# PCI-connector.net
KiCad netlist of a schematic drawn in Altium Designer
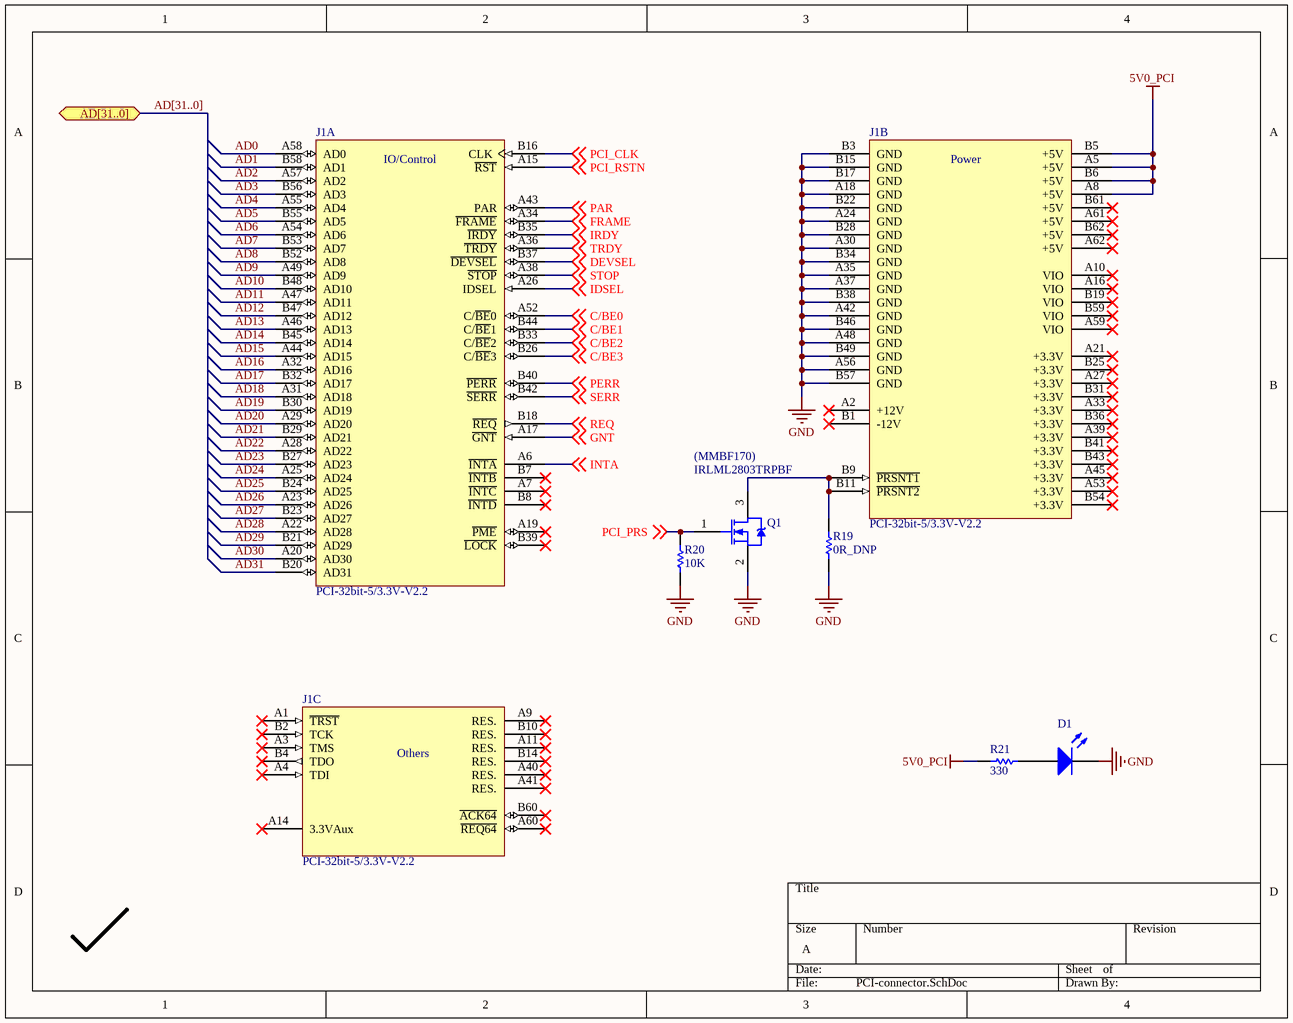
[diagram p0: PCI-connector.SchDoc]

(export (version "E")
  (design (tool "Eeschema 10.0.6"))
  (components
    (comp (ref "D1")
      (value "LED0")
      (footprint "C0805")
      (description "Typical INFRARED GaAs LED")
      (fields (field (name "PUBLISHER") "Altium Limited"))
      (libsource (lib "Miscellaneous Devices") (part "LED0"))
    )
    (comp (ref "J1")
      (value "PCI-32bit-5/3.3V-V2.2")
      (footprint "PCI-32bit-5/3.3V-V2.2")
      (libsource (lib "Conn_Schlib") (part "PCI-32bit-5/3.3V-V2.2"))
    )
    (comp (ref "Q1")
      (value "IRLML2803TRPBF")
      (footprint "SOT23")
      (description "N-Channel Power MOSFET")
      (fields (field (name "PUBLISHER") "Altium Limited"))
      (libsource (lib "Miscellaneous Devices") (part "NMOS-2"))
    )
    (comp (ref "R19")
      (value "0R_DNP")
      (footprint "0603PKG")
      (description "Semiconductor Resistor")
      (fields (field (name "Comment") "Res Semi") (field (name "PUBLISHER") "Altium Limited"))
      (libsource (lib "Miscellaneous Devices") (part "Res Semi"))
    )
    (comp (ref "R20")
      (value "10K")
      (footprint "0603PKG")
      (description "Semiconductor Resistor")
      (fields (field (name "Comment") "Res Semi") (field (name "PUBLISHER") "Altium Limited"))
      (libsource (lib "Miscellaneous Devices") (part "Res Semi"))
    )
    (comp (ref "R21")
      (value "330")
      (footprint "0603PKG")
      (description "Semiconductor Resistor")
      (fields (field (name "Comment") "Res Semi") (field (name "PUBLISHER") "Altium Limited"))
      (libsource (lib "Miscellaneous Devices") (part "Res Semi"))
    )
  )
  (nets
    (net (code "1") (name "/AD0") (class "Default")
      (node (ref "J1") (pin "A58") (pinfunction "AD0_A58") (pintype "bidirectional"))
    )
    (net (code "2") (name "/AD1") (class "Default")
      (node (ref "J1") (pin "B58") (pinfunction "AD1_B58") (pintype "bidirectional"))
    )
    (net (code "3") (name "/AD2") (class "Default")
      (node (ref "J1") (pin "A57") (pinfunction "AD2_A57") (pintype "bidirectional"))
    )
    (net (code "4") (name "/AD3") (class "Default")
      (node (ref "J1") (pin "B56") (pinfunction "AD3_B56") (pintype "bidirectional"))
    )
    (net (code "5") (name "/AD4") (class "Default")
      (node (ref "J1") (pin "A55") (pinfunction "AD4_A55") (pintype "bidirectional"))
    )
    (net (code "6") (name "/AD5") (class "Default")
      (node (ref "J1") (pin "B55") (pinfunction "AD5_B55") (pintype "bidirectional"))
    )
    (net (code "7") (name "/AD6") (class "Default")
      (node (ref "J1") (pin "A54") (pinfunction "AD6_A54") (pintype "bidirectional"))
    )
    (net (code "8") (name "/AD7") (class "Default")
      (node (ref "J1") (pin "B53") (pinfunction "AD7_B53") (pintype "bidirectional"))
    )
    (net (code "9") (name "/AD8") (class "Default")
      (node (ref "J1") (pin "B52") (pinfunction "AD8_B52") (pintype "bidirectional"))
    )
    (net (code "10") (name "/AD9") (class "Default")
      (node (ref "J1") (pin "A49") (pinfunction "AD9_A49") (pintype "bidirectional"))
    )
    (net (code "11") (name "/AD10") (class "Default")
      (node (ref "J1") (pin "B48") (pinfunction "AD10_B48") (pintype "bidirectional"))
    )
    (net (code "12") (name "/AD11") (class "Default")
      (node (ref "J1") (pin "A47") (pinfunction "AD11_A47") (pintype "bidirectional"))
    )
    (net (code "13") (name "/AD12") (class "Default")
      (node (ref "J1") (pin "B47") (pinfunction "AD12_B47") (pintype "bidirectional"))
    )
    (net (code "14") (name "/AD13") (class "Default")
      (node (ref "J1") (pin "A46") (pinfunction "AD13_A46") (pintype "bidirectional"))
    )
    (net (code "15") (name "/AD14") (class "Default")
      (node (ref "J1") (pin "B45") (pinfunction "AD14_B45") (pintype "bidirectional"))
    )
    (net (code "16") (name "/AD15") (class "Default")
      (node (ref "J1") (pin "A44") (pinfunction "AD15_A44") (pintype "bidirectional"))
    )
    (net (code "17") (name "/AD16") (class "Default")
      (node (ref "J1") (pin "A32") (pinfunction "AD16_A32") (pintype "bidirectional"))
    )
    (net (code "18") (name "/AD17") (class "Default")
      (node (ref "J1") (pin "B32") (pinfunction "AD17_B32") (pintype "bidirectional"))
    )
    (net (code "19") (name "/AD18") (class "Default")
      (node (ref "J1") (pin "A31") (pinfunction "AD18_A31") (pintype "bidirectional"))
    )
    (net (code "20") (name "/AD19") (class "Default")
      (node (ref "J1") (pin "B30") (pinfunction "AD19_B30") (pintype "bidirectional"))
    )
    (net (code "21") (name "/AD20") (class "Default")
      (node (ref "J1") (pin "A29") (pinfunction "AD20_A29") (pintype "bidirectional"))
    )
    (net (code "22") (name "/AD21") (class "Default")
      (node (ref "J1") (pin "B29") (pinfunction "AD21_B29") (pintype "bidirectional"))
    )
    (net (code "23") (name "/AD22") (class "Default")
      (node (ref "J1") (pin "A28") (pinfunction "AD22_A28") (pintype "bidirectional"))
    )
    (net (code "24") (name "/AD23") (class "Default")
      (node (ref "J1") (pin "B27") (pinfunction "AD23_B27") (pintype "bidirectional"))
    )
    (net (code "25") (name "/AD24") (class "Default")
      (node (ref "J1") (pin "A25") (pinfunction "AD24_A25") (pintype "bidirectional"))
    )
    (net (code "26") (name "/AD25") (class "Default")
      (node (ref "J1") (pin "B24") (pinfunction "AD25_B24") (pintype "bidirectional"))
    )
    (net (code "27") (name "/AD26") (class "Default")
      (node (ref "J1") (pin "A23") (pinfunction "AD26_A23") (pintype "bidirectional"))
    )
    (net (code "28") (name "/AD27") (class "Default")
      (node (ref "J1") (pin "B23") (pinfunction "AD27_B23") (pintype "bidirectional"))
    )
    (net (code "29") (name "/AD28") (class "Default")
      (node (ref "J1") (pin "A22") (pinfunction "AD28_A22") (pintype "bidirectional"))
    )
    (net (code "30") (name "/AD29") (class "Default")
      (node (ref "J1") (pin "B21") (pinfunction "AD29_B21") (pintype "bidirectional"))
    )
    (net (code "31") (name "/AD30") (class "Default")
      (node (ref "J1") (pin "A20") (pinfunction "AD30_A20") (pintype "bidirectional"))
    )
    (net (code "32") (name "/AD31") (class "Default")
      (node (ref "J1") (pin "B20") (pinfunction "AD31_B20") (pintype "bidirectional"))
    )
    (net (code "34") (name "5V0_PCI") (class "Default")
      (node (ref "J1") (pin "A5") (pinfunction "+5V_A5") (pintype "power_in"))
      (node (ref "J1") (pin "A8") (pinfunction "+5V_A8") (pintype "power_in"))
      (node (ref "J1") (pin "B5") (pinfunction "+5V_B5") (pintype "power_in"))
      (node (ref "J1") (pin "B6") (pinfunction "+5V_B6") (pintype "power_in"))
      (node (ref "R21") (pin "2") (pinfunction "2_2") (pintype "passive"))
    )
    (net (code "35") (name "C{slash}BE0") (class "Default")
      (node (ref "J1") (pin "A52") (pinfunction "C/~{BE}0_A52") (pintype "bidirectional"))
    )
    (net (code "36") (name "C{slash}BE1") (class "Default")
      (node (ref "J1") (pin "B44") (pinfunction "C/~{BE}1_B44") (pintype "bidirectional"))
    )
    (net (code "37") (name "C{slash}BE2") (class "Default")
      (node (ref "J1") (pin "B33") (pinfunction "C/~{BE}2_B33") (pintype "bidirectional"))
    )
    (net (code "38") (name "C{slash}BE3") (class "Default")
      (node (ref "J1") (pin "B26") (pinfunction "C/~{BE}3_B26") (pintype "bidirectional"))
    )
    (net (code "39") (name "DEVSEL") (class "Default")
      (node (ref "J1") (pin "B37") (pinfunction "~{DEVSEL}_B37") (pintype "bidirectional"))
    )
    (net (code "40") (name "FRAME") (class "Default")
      (node (ref "J1") (pin "A34") (pinfunction "~{FRAME}_A34") (pintype "bidirectional"))
    )
    (net (code "41") (name "GND") (class "Default")
      (node (ref "D1") (pin "2") (pinfunction "K_2") (pintype "passive"))
      (node (ref "J1") (pin "A18") (pinfunction "GND_A18") (pintype "power_in"))
      (node (ref "J1") (pin "A24") (pinfunction "GND_A24") (pintype "power_in"))
      (node (ref "J1") (pin "A30") (pinfunction "GND_A30") (pintype "power_in"))
      (node (ref "J1") (pin "A35") (pinfunction "GND_A35") (pintype "power_in"))
      (node (ref "J1") (pin "A37") (pinfunction "GND_A37") (pintype "power_in"))
      (node (ref "J1") (pin "A42") (pinfunction "GND_A42") (pintype "power_in"))
      (node (ref "J1") (pin "A48") (pinfunction "GND_A48") (pintype "power_in"))
      (node (ref "J1") (pin "A56") (pinfunction "GND_A56") (pintype "power_in"))
      (node (ref "J1") (pin "B15") (pinfunction "GND_B15") (pintype "power_in"))
      (node (ref "J1") (pin "B17") (pinfunction "GND_B17") (pintype "power_in"))
      (node (ref "J1") (pin "B22") (pinfunction "GND_B22") (pintype "power_in"))
      (node (ref "J1") (pin "B28") (pinfunction "GND_B28") (pintype "power_in"))
      (node (ref "J1") (pin "B3") (pinfunction "GND_B3") (pintype "power_in"))
      (node (ref "J1") (pin "B34") (pinfunction "GND_B34") (pintype "power_in"))
      (node (ref "J1") (pin "B38") (pinfunction "GND_B38") (pintype "power_in"))
      (node (ref "J1") (pin "B46") (pinfunction "GND_B46") (pintype "power_in"))
      (node (ref "J1") (pin "B49") (pinfunction "GND_B49") (pintype "power_in"))
      (node (ref "J1") (pin "B57") (pinfunction "GND_B57") (pintype "power_in"))
      (node (ref "Q1") (pin "2") (pinfunction "S_2") (pintype "passive"))
      (node (ref "R19") (pin "2") (pinfunction "2_2") (pintype "passive"))
      (node (ref "R20") (pin "2") (pinfunction "2_2") (pintype "passive"))
    )
    (net (code "42") (name "GNT") (class "Default")
      (node (ref "J1") (pin "A17") (pinfunction "~{GNT}_A17") (pintype "input"))
    )
    (net (code "43") (name "IDSEL") (class "Default")
      (node (ref "J1") (pin "A26") (pinfunction "IDSEL_A26") (pintype "input"))
    )
    (net (code "44") (name "INTA") (class "Default")
      (node (ref "J1") (pin "A6") (pinfunction "~{INTA}_A6") (pintype "open_collector"))
    )
    (net (code "45") (name "IRDY") (class "Default")
      (node (ref "J1") (pin "B35") (pinfunction "~{IRDY}_B35") (pintype "bidirectional"))
    )
    (net (code "46") (name "Net-(D1-A)") (class "Default")
      (node (ref "D1") (pin "1") (pinfunction "A_1") (pintype "passive"))
      (node (ref "R21") (pin "1") (pinfunction "1_1") (pintype "passive"))
    )
    (net (code "47") (name "Net-(J1B-~{PRSNT1})") (class "Default")
      (node (ref "J1") (pin "B11") (pinfunction "~{PRSNT2}_B11") (pintype "input"))
      (node (ref "J1") (pin "B9") (pinfunction "~{PRSNT1}_B9") (pintype "input"))
      (node (ref "Q1") (pin "3") (pinfunction "D_3") (pintype "passive"))
      (node (ref "R19") (pin "1") (pinfunction "1_1") (pintype "passive"))
    )
    (net (code "48") (name "PAR") (class "Default")
      (node (ref "J1") (pin "A43") (pinfunction "PAR_A43") (pintype "bidirectional"))
    )
    (net (code "49") (name "PCI_CLK") (class "Default")
      (node (ref "J1") (pin "B16") (pinfunction "CLK_B16") (pintype "input"))
    )
    (net (code "50") (name "PCI_PRS") (class "Default")
      (node (ref "Q1") (pin "1") (pinfunction "G_1") (pintype "passive"))
      (node (ref "R20") (pin "1") (pinfunction "1_1") (pintype "passive"))
    )
    (net (code "51") (name "PCI_RSTN") (class "Default")
      (node (ref "J1") (pin "A15") (pinfunction "~{RST}_A15") (pintype "input"))
    )
    (net (code "52") (name "PERR") (class "Default")
      (node (ref "J1") (pin "B40") (pinfunction "~{PERR}_B40") (pintype "bidirectional"))
    )
    (net (code "53") (name "REQ") (class "Default")
      (node (ref "J1") (pin "B18") (pinfunction "~{REQ}_B18") (pintype "output"))
    )
    (net (code "54") (name "SERR") (class "Default")
      (node (ref "J1") (pin "B42") (pinfunction "~{SERR}_B42") (pintype "bidirectional"))
    )
    (net (code "55") (name "STOP") (class "Default")
      (node (ref "J1") (pin "A38") (pinfunction "~{STOP}_A38") (pintype "bidirectional"))
    )
    (net (code "56") (name "TRDY") (class "Default")
      (node (ref "J1") (pin "A36") (pinfunction "~{TRDY}_A36") (pintype "bidirectional"))
    )
    (net (code "57") (name "unconnected-(J1A-~{INTB}-PadB7)") (class "Default")
      (node (ref "J1") (pin "B7") (pinfunction "~{INTB}_B7") (pintype "open_collector+no_connect"))
    )
    (net (code "58") (name "unconnected-(J1A-~{INTC}-PadA7)") (class "Default")
      (node (ref "J1") (pin "A7") (pinfunction "~{INTC}_A7") (pintype "open_collector+no_connect"))
    )
    (net (code "59") (name "unconnected-(J1A-~{INTD}-PadB8)") (class "Default")
      (node (ref "J1") (pin "B8") (pinfunction "~{INTD}_B8") (pintype "open_collector+no_connect"))
    )
    (net (code "60") (name "unconnected-(J1A-~{LOCK}-PadB39)") (class "Default")
      (node (ref "J1") (pin "B39") (pinfunction "~{LOCK}_B39") (pintype "bidirectional+no_connect"))
    )
    (net (code "61") (name "unconnected-(J1A-~{PME}-PadA19)") (class "Default")
      (node (ref "J1") (pin "A19") (pinfunction "~{PME}_A19") (pintype "bidirectional+no_connect"))
    )
    (net (code "62") (name "unconnected-(J1B-+3.3V-PadA21)") (class "Default")
      (node (ref "J1") (pin "A21") (pinfunction "+3.3V_A21") (pintype "power_in+no_connect"))
    )
    (net (code "63") (name "unconnected-(J1B-+3.3V-PadA27)") (class "Default")
      (node (ref "J1") (pin "A27") (pinfunction "+3.3V_A27") (pintype "power_in+no_connect"))
    )
    (net (code "64") (name "unconnected-(J1B-+3.3V-PadA33)") (class "Default")
      (node (ref "J1") (pin "A33") (pinfunction "+3.3V_A33") (pintype "power_in+no_connect"))
    )
    (net (code "65") (name "unconnected-(J1B-+3.3V-PadA39)") (class "Default")
      (node (ref "J1") (pin "A39") (pinfunction "+3.3V_A39") (pintype "power_in+no_connect"))
    )
    (net (code "66") (name "unconnected-(J1B-+3.3V-PadA45)") (class "Default")
      (node (ref "J1") (pin "A45") (pinfunction "+3.3V_A45") (pintype "power_in+no_connect"))
    )
    (net (code "67") (name "unconnected-(J1B-+3.3V-PadA53)") (class "Default")
      (node (ref "J1") (pin "A53") (pinfunction "+3.3V_A53") (pintype "power_in+no_connect"))
    )
    (net (code "68") (name "unconnected-(J1B-+3.3V-PadB25)") (class "Default")
      (node (ref "J1") (pin "B25") (pinfunction "+3.3V_B25") (pintype "power_in+no_connect"))
    )
    (net (code "69") (name "unconnected-(J1B-+3.3V-PadB31)") (class "Default")
      (node (ref "J1") (pin "B31") (pinfunction "+3.3V_B31") (pintype "power_in+no_connect"))
    )
    (net (code "70") (name "unconnected-(J1B-+3.3V-PadB36)") (class "Default")
      (node (ref "J1") (pin "B36") (pinfunction "+3.3V_B36") (pintype "power_in+no_connect"))
    )
    (net (code "71") (name "unconnected-(J1B-+3.3V-PadB41)") (class "Default")
      (node (ref "J1") (pin "B41") (pinfunction "+3.3V_B41") (pintype "power_in+no_connect"))
    )
    (net (code "72") (name "unconnected-(J1B-+3.3V-PadB43)") (class "Default")
      (node (ref "J1") (pin "B43") (pinfunction "+3.3V_B43") (pintype "power_in+no_connect"))
    )
    (net (code "73") (name "unconnected-(J1B-+3.3V-PadB54)") (class "Default")
      (node (ref "J1") (pin "B54") (pinfunction "+3.3V_B54") (pintype "power_in+no_connect"))
    )
    (net (code "74") (name "unconnected-(J1B-+5V-PadA61)") (class "Default")
      (node (ref "J1") (pin "A61") (pinfunction "+5V_A61") (pintype "power_in+no_connect"))
    )
    (net (code "75") (name "unconnected-(J1B-+5V-PadA62)") (class "Default")
      (node (ref "J1") (pin "A62") (pinfunction "+5V_A62") (pintype "power_in+no_connect"))
    )
    (net (code "76") (name "unconnected-(J1B-+5V-PadB61)") (class "Default")
      (node (ref "J1") (pin "B61") (pinfunction "+5V_B61") (pintype "power_in+no_connect"))
    )
    (net (code "77") (name "unconnected-(J1B-+5V-PadB62)") (class "Default")
      (node (ref "J1") (pin "B62") (pinfunction "+5V_B62") (pintype "power_in+no_connect"))
    )
    (net (code "78") (name "unconnected-(J1B-+12V-PadA2)") (class "Default")
      (node (ref "J1") (pin "A2") (pinfunction "+12V_A2") (pintype "power_in+no_connect"))
    )
    (net (code "79") (name "unconnected-(J1B--12V-PadB1)") (class "Default")
      (node (ref "J1") (pin "B1") (pinfunction "-12V_B1") (pintype "power_in+no_connect"))
    )
    (net (code "80") (name "unconnected-(J1B-VIO-PadA10)") (class "Default")
      (node (ref "J1") (pin "A10") (pinfunction "VIO_A10") (pintype "power_in+no_connect"))
    )
    (net (code "81") (name "unconnected-(J1B-VIO-PadA16)") (class "Default")
      (node (ref "J1") (pin "A16") (pinfunction "VIO_A16") (pintype "power_in+no_connect"))
    )
    (net (code "82") (name "unconnected-(J1B-VIO-PadA59)") (class "Default")
      (node (ref "J1") (pin "A59") (pinfunction "VIO_A59") (pintype "power_in+no_connect"))
    )
    (net (code "83") (name "unconnected-(J1B-VIO-PadB19)") (class "Default")
      (node (ref "J1") (pin "B19") (pinfunction "VIO_B19") (pintype "power_in+no_connect"))
    )
    (net (code "84") (name "unconnected-(J1B-VIO-PadB59)") (class "Default")
      (node (ref "J1") (pin "B59") (pinfunction "VIO_B59") (pintype "power_in+no_connect"))
    )
    (net (code "85") (name "unconnected-(J1C-3.3VAux-PadA14)") (class "Default")
      (node (ref "J1") (pin "A14") (pinfunction "3.3VAux_A14") (pintype "power_in+no_connect"))
    )
    (net (code "86") (name "unconnected-(J1C-RES.-PadA9)") (class "Default")
      (node (ref "J1") (pin "A9") (pinfunction "RES._A9") (pintype "passive+no_connect"))
    )
    (net (code "87") (name "unconnected-(J1C-RES.-PadA11)") (class "Default")
      (node (ref "J1") (pin "A11") (pinfunction "RES._A11") (pintype "passive+no_connect"))
    )
    (net (code "88") (name "unconnected-(J1C-RES.-PadA40)") (class "Default")
      (node (ref "J1") (pin "A40") (pinfunction "RES._A40") (pintype "passive+no_connect"))
    )
    (net (code "89") (name "unconnected-(J1C-RES.-PadA41)") (class "Default")
      (node (ref "J1") (pin "A41") (pinfunction "RES._A41") (pintype "passive+no_connect"))
    )
    (net (code "90") (name "unconnected-(J1C-RES.-PadB10)") (class "Default")
      (node (ref "J1") (pin "B10") (pinfunction "RES._B10") (pintype "passive+no_connect"))
    )
    (net (code "91") (name "unconnected-(J1C-RES.-PadB14)") (class "Default")
      (node (ref "J1") (pin "B14") (pinfunction "RES._B14") (pintype "passive+no_connect"))
    )
    (net (code "92") (name "unconnected-(J1C-TCK-PadB2)") (class "Default")
      (node (ref "J1") (pin "B2") (pinfunction "TCK_B2") (pintype "input+no_connect"))
    )
    (net (code "93") (name "unconnected-(J1C-TDI-PadA4)") (class "Default")
      (node (ref "J1") (pin "A4") (pinfunction "TDI_A4") (pintype "input+no_connect"))
    )
    (net (code "94") (name "unconnected-(J1C-TDO-PadB4)") (class "Default")
      (node (ref "J1") (pin "B4") (pinfunction "TDO_B4") (pintype "output+no_connect"))
    )
    (net (code "95") (name "unconnected-(J1C-TMS-PadA3)") (class "Default")
      (node (ref "J1") (pin "A3") (pinfunction "TMS_A3") (pintype "input+no_connect"))
    )
    (net (code "96") (name "unconnected-(J1C-~{ACK64}-PadB60)") (class "Default")
      (node (ref "J1") (pin "B60") (pinfunction "~{ACK64}_B60") (pintype "bidirectional+no_connect"))
    )
    (net (code "97") (name "unconnected-(J1C-~{REQ64}-PadA60)") (class "Default")
      (node (ref "J1") (pin "A60") (pinfunction "~{REQ64}_A60") (pintype "bidirectional+no_connect"))
    )
    (net (code "98") (name "unconnected-(J1C-~{TRST}-PadA1)") (class "Default")
      (node (ref "J1") (pin "A1") (pinfunction "~{TRST}_A1") (pintype "input+no_connect"))
    )
  )
)
